# 06-modem0.net
KiCad netlist of a schematic drawn in Altium Designer
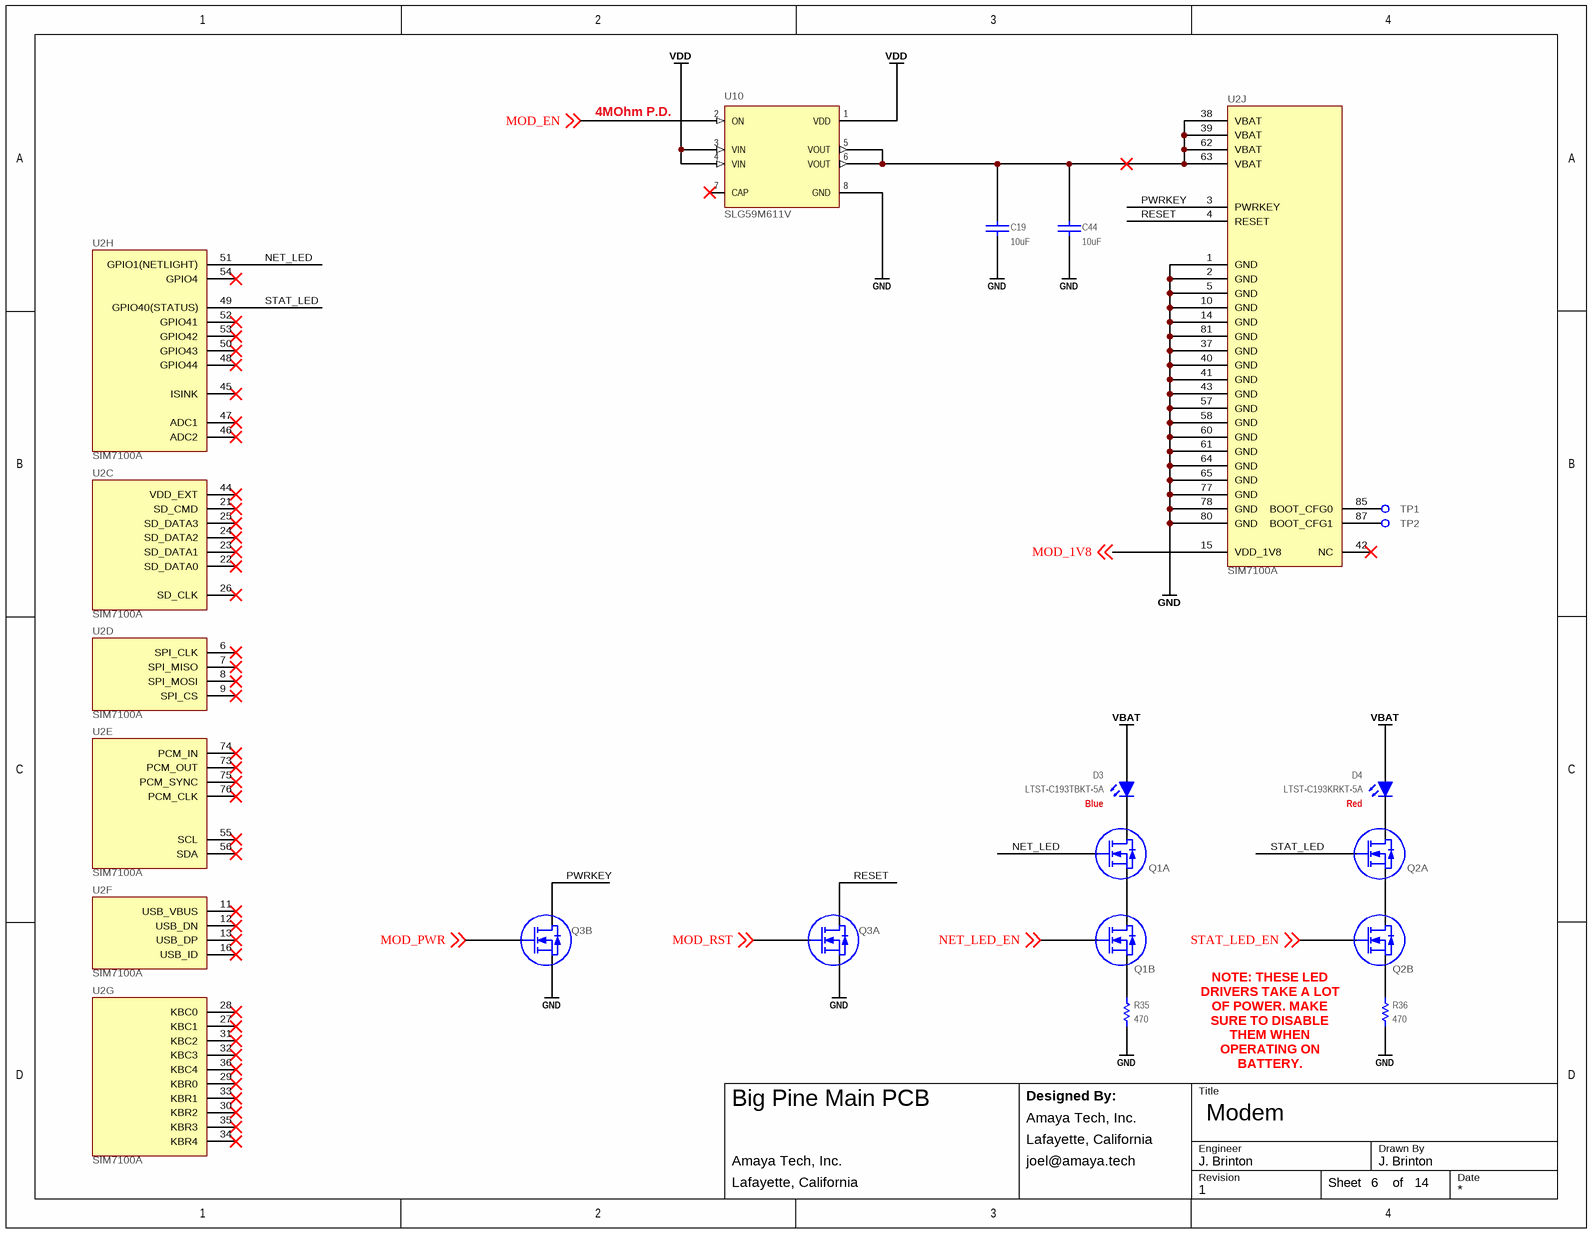
[diagram p0: 06-modem0.SchDoc]

(export (version "E")
  (design (tool "Eeschema 10.0.6"))
  (components
    (comp (ref "C19")
      (value "10uF")
      (footprint "CAPC160X80X90L20N")
      (description "Ceramic Capacitor 10uF ±20% 25V X5R 0603")
      (fields (field (name "MANUFACTURER") "Murata") (field (name "VOLTAGE") "25V"))
      (libsource (lib "generic") (part "CAP 0603"))
    )
    (comp (ref "C44")
      (value "10uF")
      (footprint "CAPC160X80X90L20N")
      (description "Ceramic Capacitor 10uF ±20% 25V X5R 0603")
      (fields (field (name "MANUFACTURER") "Murata") (field (name "VOLTAGE") "25V"))
      (libsource (lib "generic") (part "CAP 0603"))
    )
    (comp (ref "D3")
      (value "LTST-C193TBKT-5A")
      (footprint "0603_LED")
      (description "LED, SMT 0603, Color Blue, 5mA, 2.8V")
      (fields (field (name "MANUFACTURER") "Lite-On"))
      (libsource (lib "generic") (part "LED0603GR"))
    )
    (comp (ref "D4")
      (value "LTST-C193KRKT-5A")
      (footprint "0603_LED")
      (description "LED, SMT 0603, Color Red, 5mA, 2V")
      (fields (field (name "MANUFACTURER") "Lite-On"))
      (libsource (lib "generic") (part "LED0603Y"))
    )
    (comp (ref "Q1")
      (value "UM6K34NTCN")
      (footprint "SOT363")
      (description "Dual N-Channel Enhancement Mode MOSFET")
      (fields (field (name "MANUFACTURER") "Rohm"))
      (libsource (lib "diodes_inc") (part "2N7002DW-7-F"))
    )
    (comp (ref "Q2")
      (value "UM6K34NTCN")
      (footprint "SOT363")
      (description "Dual N-Channel Enhancement Mode MOSFET")
      (fields (field (name "MANUFACTURER") "Rohm"))
      (libsource (lib "diodes_inc") (part "2N7002DW-7-F"))
    )
    (comp (ref "Q3")
      (value "UM6K34NTCN")
      (footprint "SOT363")
      (description "Dual N-Channel Enhancement Mode MOSFET")
      (fields (field (name "MANUFACTURER") "Rohm"))
      (libsource (lib "diodes_inc") (part "2N7002DW-7-F"))
    )
    (comp (ref "R35")
      (value "470")
      (footprint "RESC2012X70N")
      (description "Thick Film Resistor 470 ±1% 0805")
      (fields (field (name "MANUFACTURER") "Panasonic") (field (name "TOLERANCE") "±1%"))
      (libsource (lib "Graviton") (part "RES 0402"))
    )
    (comp (ref "R36")
      (value "470")
      (footprint "RESC2012X70N")
      (description "Thick Film Resistor 470 ±1% 0805")
      (fields (field (name "MANUFACTURER") "Panasonic") (field (name "TOLERANCE") "±1%"))
      (libsource (lib "Graviton") (part "RES 0402"))
    )
    (comp (ref "TP1")
      (value "TEST_POINT_SMD_10")
      (footprint "generic:TEST_POINT_SMD_10")
      (description "Test Point SMD")
      (libsource (lib "generic") (part "TEST_POINT_SMD_10"))
    )
    (comp (ref "TP2")
      (value "TEST_POINT_SMD_10")
      (footprint "generic:TEST_POINT_SMD_10")
      (description "Test Point SMD")
      (libsource (lib "generic") (part "TEST_POINT_SMD_10"))
    )
    (comp (ref "U2")
      (value "SIM7100A")
      (footprint "SIM7100A")
      (description "Cellular Module")
      (fields (field (name "MANUFACTURER") "SIMCOM"))
      (libsource (lib "simcom") (part "Component_1"))
    )
    (comp (ref "U10")
      (value "SLG59M611V")
      (footprint "DFN200X150X80-8N")
      (description "High-Side Load Switch")
      (fields (field (name "MANUFACTURER") "Silego"))
      (libsource (lib "silego") (part "SLG59M611V"))
    )
  )
  (nets
    (net (code "1") (name "/NET_LED") (class "Default")
      (node (ref "Q1") (pin "5") (pinfunction "G1_5") (pintype "passive"))
      (node (ref "U2") (pin "51") (pinfunction "GPIO1(NETLIGHT)_51") (pintype "passive"))
    )
    (net (code "2") (name "/PWRKEY") (class "Default")
      (node (ref "Q3") (pin "6") (pinfunction "D2_6") (pintype "passive"))
      (node (ref "U2") (pin "3") (pinfunction "PWRKEY_3") (pintype "passive"))
    )
    (net (code "3") (name "/RESET") (class "Default")
      (node (ref "Q3") (pin "3") (pinfunction "D1_3") (pintype "passive"))
      (node (ref "U2") (pin "4") (pinfunction "RESET_4") (pintype "passive"))
    )
    (net (code "4") (name "/STAT_LED") (class "Default")
      (node (ref "Q2") (pin "5") (pinfunction "G1_5") (pintype "passive"))
      (node (ref "U2") (pin "49") (pinfunction "GPIO40(STATUS)_49") (pintype "passive"))
    )
    (net (code "5") (name "GND") (class "Default")
      (node (ref "C19") (pin "1") (pinfunction "1_1") (pintype "passive"))
      (node (ref "C44") (pin "1") (pinfunction "1_1") (pintype "passive"))
      (node (ref "Q3") (pin "1") (pinfunction "S2_1") (pintype "passive"))
      (node (ref "Q3") (pin "4") (pinfunction "S1_4") (pintype "passive"))
      (node (ref "R35") (pin "1") (pinfunction "1_1") (pintype "passive"))
      (node (ref "R36") (pin "1") (pinfunction "1_1") (pintype "passive"))
      (node (ref "U10") (pin "8") (pinfunction "GND_8") (pintype "power_in"))
      (node (ref "U2") (pin "1") (pinfunction "GND_1") (pintype "power_in"))
      (node (ref "U2") (pin "10") (pinfunction "GND_10") (pintype "power_in"))
      (node (ref "U2") (pin "14") (pinfunction "GND_14") (pintype "power_in"))
      (node (ref "U2") (pin "2") (pinfunction "GND_2") (pintype "power_in"))
      (node (ref "U2") (pin "37") (pinfunction "GND_37") (pintype "power_in"))
      (node (ref "U2") (pin "40") (pinfunction "GND_40") (pintype "power_in"))
      (node (ref "U2") (pin "41") (pinfunction "GND_41") (pintype "power_in"))
      (node (ref "U2") (pin "43") (pinfunction "GND_43") (pintype "power_in"))
      (node (ref "U2") (pin "5") (pinfunction "GND_5") (pintype "power_in"))
      (node (ref "U2") (pin "57") (pinfunction "GND_57") (pintype "power_in"))
      (node (ref "U2") (pin "58") (pinfunction "GND_58") (pintype "power_in"))
      (node (ref "U2") (pin "60") (pinfunction "GND_60") (pintype "power_in"))
      (node (ref "U2") (pin "61") (pinfunction "GND_61") (pintype "power_in"))
      (node (ref "U2") (pin "64") (pinfunction "GND_64") (pintype "power_in"))
      (node (ref "U2") (pin "65") (pinfunction "GND_65") (pintype "power_in"))
      (node (ref "U2") (pin "77") (pinfunction "GND_77") (pintype "power_in"))
      (node (ref "U2") (pin "78") (pinfunction "GND_78") (pintype "power_in"))
      (node (ref "U2") (pin "80") (pinfunction "GND_80") (pintype "power_in"))
      (node (ref "U2") (pin "81") (pinfunction "GND_81") (pintype "power_in"))
    )
    (net (code "6") (name "MOD_1V8") (class "Default")
      (node (ref "U2") (pin "15") (pinfunction "VDD_1V8_15") (pintype "power_in"))
    )
    (net (code "7") (name "MOD_EN") (class "Default")
      (node (ref "U10") (pin "2") (pinfunction "ON_2") (pintype "input"))
    )
    (net (code "8") (name "MOD_PWR") (class "Default")
      (node (ref "Q3") (pin "2") (pinfunction "G2_2") (pintype "passive"))
    )
    (net (code "9") (name "MOD_RST") (class "Default")
      (node (ref "Q3") (pin "5") (pinfunction "G1_5") (pintype "passive"))
    )
    (net (code "10") (name "NET_LED_EN") (class "Default")
      (node (ref "Q1") (pin "2") (pinfunction "G2_2") (pintype "passive"))
    )
    (net (code "11") (name "Net-(C19-Pad2)") (class "Default")
      (node (ref "C19") (pin "2") (pinfunction "2_2") (pintype "passive"))
      (node (ref "C44") (pin "2") (pinfunction "2_2") (pintype "passive"))
      (node (ref "U10") (pin "5") (pinfunction "VOUT_5") (pintype "output"))
      (node (ref "U10") (pin "6") (pinfunction "VOUT_6") (pintype "output"))
      (node (ref "U2") (pin "38") (pinfunction "VBAT_38") (pintype "power_in"))
      (node (ref "U2") (pin "39") (pinfunction "VBAT_39") (pintype "power_in"))
      (node (ref "U2") (pin "62") (pinfunction "VBAT_62") (pintype "power_in"))
      (node (ref "U2") (pin "63") (pinfunction "VBAT_63") (pintype "power_in"))
    )
    (net (code "12") (name "Net-(D3-K)") (class "Default")
      (node (ref "D3") (pin "2") (pinfunction "K_2") (pintype "passive"))
      (node (ref "Q1") (pin "3") (pinfunction "D1_3") (pintype "passive"))
    )
    (net (code "13") (name "Net-(D4-K)") (class "Default")
      (node (ref "D4") (pin "2") (pinfunction "K_2") (pintype "passive"))
      (node (ref "Q2") (pin "3") (pinfunction "D1_3") (pintype "passive"))
    )
    (net (code "14") (name "Net-(Q1A-S1)") (class "Default")
      (node (ref "Q1") (pin "4") (pinfunction "S1_4") (pintype "passive"))
      (node (ref "Q1") (pin "6") (pinfunction "D2_6") (pintype "passive"))
    )
    (net (code "15") (name "Net-(Q1B-S2)") (class "Default")
      (node (ref "Q1") (pin "1") (pinfunction "S2_1") (pintype "passive"))
      (node (ref "R35") (pin "2") (pinfunction "2_2") (pintype "passive"))
    )
    (net (code "16") (name "Net-(Q2A-S1)") (class "Default")
      (node (ref "Q2") (pin "4") (pinfunction "S1_4") (pintype "passive"))
      (node (ref "Q2") (pin "6") (pinfunction "D2_6") (pintype "passive"))
    )
    (net (code "17") (name "Net-(Q2B-S2)") (class "Default")
      (node (ref "Q2") (pin "1") (pinfunction "S2_1") (pintype "passive"))
      (node (ref "R36") (pin "2") (pinfunction "2_2") (pintype "passive"))
    )
    (net (code "18") (name "Net-(U2J-BOOT_CFG0)") (class "Default")
      (node (ref "TP1") (pin "1") (pinfunction "1_1") (pintype "passive"))
      (node (ref "U2") (pin "85") (pinfunction "BOOT_CFG0_85") (pintype "passive"))
    )
    (net (code "19") (name "Net-(U2J-BOOT_CFG1)") (class "Default")
      (node (ref "TP2") (pin "1") (pinfunction "1_1") (pintype "passive"))
      (node (ref "U2") (pin "87") (pinfunction "BOOT_CFG1_87") (pintype "passive"))
    )
    (net (code "20") (name "STAT_LED_EN") (class "Default")
      (node (ref "Q2") (pin "2") (pinfunction "G2_2") (pintype "passive"))
    )
    (net (code "21") (name "VBAT") (class "Default")
      (node (ref "D3") (pin "1") (pinfunction "A_1") (pintype "passive"))
      (node (ref "D4") (pin "1") (pinfunction "A_1") (pintype "passive"))
    )
    (net (code "22") (name "VDD") (class "Default")
      (node (ref "U10") (pin "1") (pinfunction "VDD_1") (pintype "power_in"))
      (node (ref "U10") (pin "3") (pinfunction "VIN_3") (pintype "input"))
      (node (ref "U10") (pin "4") (pinfunction "VIN_4") (pintype "input"))
    )
    (net (code "23") (name "unconnected-(U2C-SD_CLK-Pad26)") (class "Default")
      (node (ref "U2") (pin "26") (pinfunction "SD_CLK_26") (pintype "passive+no_connect"))
    )
    (net (code "24") (name "unconnected-(U2C-SD_CMD-Pad21)") (class "Default")
      (node (ref "U2") (pin "21") (pinfunction "SD_CMD_21") (pintype "passive+no_connect"))
    )
    (net (code "25") (name "unconnected-(U2C-SD_DATA0-Pad22)") (class "Default")
      (node (ref "U2") (pin "22") (pinfunction "SD_DATA0_22") (pintype "passive+no_connect"))
    )
    (net (code "26") (name "unconnected-(U2C-SD_DATA1-Pad23)") (class "Default")
      (node (ref "U2") (pin "23") (pinfunction "SD_DATA1_23") (pintype "passive+no_connect"))
    )
    (net (code "27") (name "unconnected-(U2C-SD_DATA2-Pad24)") (class "Default")
      (node (ref "U2") (pin "24") (pinfunction "SD_DATA2_24") (pintype "passive+no_connect"))
    )
    (net (code "28") (name "unconnected-(U2C-SD_DATA3-Pad25)") (class "Default")
      (node (ref "U2") (pin "25") (pinfunction "SD_DATA3_25") (pintype "passive+no_connect"))
    )
    (net (code "29") (name "unconnected-(U2C-VDD_EXT-Pad44)") (class "Default")
      (node (ref "U2") (pin "44") (pinfunction "VDD_EXT_44") (pintype "power_in+no_connect"))
    )
    (net (code "30") (name "unconnected-(U2D-SPI_CLK-Pad6)") (class "Default")
      (node (ref "U2") (pin "6") (pinfunction "SPI_CLK_6") (pintype "passive+no_connect"))
    )
    (net (code "31") (name "unconnected-(U2D-SPI_CS-Pad9)") (class "Default")
      (node (ref "U2") (pin "9") (pinfunction "SPI_CS_9") (pintype "passive+no_connect"))
    )
    (net (code "32") (name "unconnected-(U2D-SPI_MISO-Pad7)") (class "Default")
      (node (ref "U2") (pin "7") (pinfunction "SPI_MISO_7") (pintype "passive+no_connect"))
    )
    (net (code "33") (name "unconnected-(U2D-SPI_MOSI-Pad8)") (class "Default")
      (node (ref "U2") (pin "8") (pinfunction "SPI_MOSI_8") (pintype "passive+no_connect"))
    )
    (net (code "34") (name "unconnected-(U2E-PCM_CLK-Pad76)") (class "Default")
      (node (ref "U2") (pin "76") (pinfunction "PCM_CLK_76") (pintype "passive+no_connect"))
    )
    (net (code "35") (name "unconnected-(U2E-PCM_IN-Pad74)") (class "Default")
      (node (ref "U2") (pin "74") (pinfunction "PCM_IN_74") (pintype "passive+no_connect"))
    )
    (net (code "36") (name "unconnected-(U2E-PCM_OUT-Pad73)") (class "Default")
      (node (ref "U2") (pin "73") (pinfunction "PCM_OUT_73") (pintype "passive+no_connect"))
    )
    (net (code "37") (name "unconnected-(U2E-PCM_SYNC-Pad75)") (class "Default")
      (node (ref "U2") (pin "75") (pinfunction "PCM_SYNC_75") (pintype "passive+no_connect"))
    )
    (net (code "38") (name "unconnected-(U2E-SCL-Pad55)") (class "Default")
      (node (ref "U2") (pin "55") (pinfunction "SCL_55") (pintype "passive+no_connect"))
    )
    (net (code "39") (name "unconnected-(U2E-SDA-Pad56)") (class "Default")
      (node (ref "U2") (pin "56") (pinfunction "SDA_56") (pintype "passive+no_connect"))
    )
    (net (code "40") (name "unconnected-(U2F-USB_DN-Pad12)") (class "Default")
      (node (ref "U2") (pin "12") (pinfunction "USB_DN_12") (pintype "passive+no_connect"))
    )
    (net (code "41") (name "unconnected-(U2F-USB_DP-Pad13)") (class "Default")
      (node (ref "U2") (pin "13") (pinfunction "USB_DP_13") (pintype "passive+no_connect"))
    )
    (net (code "42") (name "unconnected-(U2F-USB_ID-Pad16)") (class "Default")
      (node (ref "U2") (pin "16") (pinfunction "USB_ID_16") (pintype "passive+no_connect"))
    )
    (net (code "43") (name "unconnected-(U2F-USB_VBUS-Pad11)") (class "Default")
      (node (ref "U2") (pin "11") (pinfunction "USB_VBUS_11") (pintype "passive+no_connect"))
    )
    (net (code "44") (name "unconnected-(U2G-KBC0-Pad28)") (class "Default")
      (node (ref "U2") (pin "28") (pinfunction "KBC0_28") (pintype "passive+no_connect"))
    )
    (net (code "45") (name "unconnected-(U2G-KBC1-Pad27)") (class "Default")
      (node (ref "U2") (pin "27") (pinfunction "KBC1_27") (pintype "passive+no_connect"))
    )
    (net (code "46") (name "unconnected-(U2G-KBC2-Pad31)") (class "Default")
      (node (ref "U2") (pin "31") (pinfunction "KBC2_31") (pintype "passive+no_connect"))
    )
    (net (code "47") (name "unconnected-(U2G-KBC3-Pad32)") (class "Default")
      (node (ref "U2") (pin "32") (pinfunction "KBC3_32") (pintype "passive+no_connect"))
    )
    (net (code "48") (name "unconnected-(U2G-KBC4-Pad36)") (class "Default")
      (node (ref "U2") (pin "36") (pinfunction "KBC4_36") (pintype "passive+no_connect"))
    )
    (net (code "49") (name "unconnected-(U2G-KBR0-Pad29)") (class "Default")
      (node (ref "U2") (pin "29") (pinfunction "KBR0_29") (pintype "passive+no_connect"))
    )
    (net (code "50") (name "unconnected-(U2G-KBR1-Pad33)") (class "Default")
      (node (ref "U2") (pin "33") (pinfunction "KBR1_33") (pintype "passive+no_connect"))
    )
    (net (code "51") (name "unconnected-(U2G-KBR2-Pad30)") (class "Default")
      (node (ref "U2") (pin "30") (pinfunction "KBR2_30") (pintype "passive+no_connect"))
    )
    (net (code "52") (name "unconnected-(U2G-KBR3-Pad35)") (class "Default")
      (node (ref "U2") (pin "35") (pinfunction "KBR3_35") (pintype "passive+no_connect"))
    )
    (net (code "53") (name "unconnected-(U2G-KBR4-Pad34)") (class "Default")
      (node (ref "U2") (pin "34") (pinfunction "KBR4_34") (pintype "passive+no_connect"))
    )
    (net (code "54") (name "unconnected-(U2H-ADC1-Pad47)") (class "Default")
      (node (ref "U2") (pin "47") (pinfunction "ADC1_47") (pintype "passive+no_connect"))
    )
    (net (code "55") (name "unconnected-(U2H-ADC2-Pad46)") (class "Default")
      (node (ref "U2") (pin "46") (pinfunction "ADC2_46") (pintype "passive+no_connect"))
    )
    (net (code "56") (name "unconnected-(U2H-GPIO4-Pad54)") (class "Default")
      (node (ref "U2") (pin "54") (pinfunction "GPIO4_54") (pintype "passive+no_connect"))
    )
    (net (code "57") (name "unconnected-(U2H-GPIO41-Pad52)") (class "Default")
      (node (ref "U2") (pin "52") (pinfunction "GPIO41_52") (pintype "passive+no_connect"))
    )
    (net (code "58") (name "unconnected-(U2H-GPIO42-Pad53)") (class "Default")
      (node (ref "U2") (pin "53") (pinfunction "GPIO42_53") (pintype "passive+no_connect"))
    )
    (net (code "59") (name "unconnected-(U2H-GPIO43-Pad50)") (class "Default")
      (node (ref "U2") (pin "50") (pinfunction "GPIO43_50") (pintype "passive+no_connect"))
    )
    (net (code "60") (name "unconnected-(U2H-GPIO44-Pad48)") (class "Default")
      (node (ref "U2") (pin "48") (pinfunction "GPIO44_48") (pintype "passive+no_connect"))
    )
    (net (code "61") (name "unconnected-(U2H-ISINK-Pad45)") (class "Default")
      (node (ref "U2") (pin "45") (pinfunction "ISINK_45") (pintype "passive+no_connect"))
    )
    (net (code "62") (name "unconnected-(U2J-NC-Pad42)") (class "Default")
      (node (ref "U2") (pin "42") (pinfunction "NC_42") (pintype "passive+no_connect"))
    )
    (net (code "63") (name "unconnected-(U10-CAP-Pad7)") (class "Default")
      (node (ref "U10") (pin "7") (pinfunction "CAP_7") (pintype "passive+no_connect"))
    )
  )
)
